# ProProject_FAB-O-MATIC___a_FabLab_machin.net
KiCad netlist of a schematic drawn in EasyEDA Pro
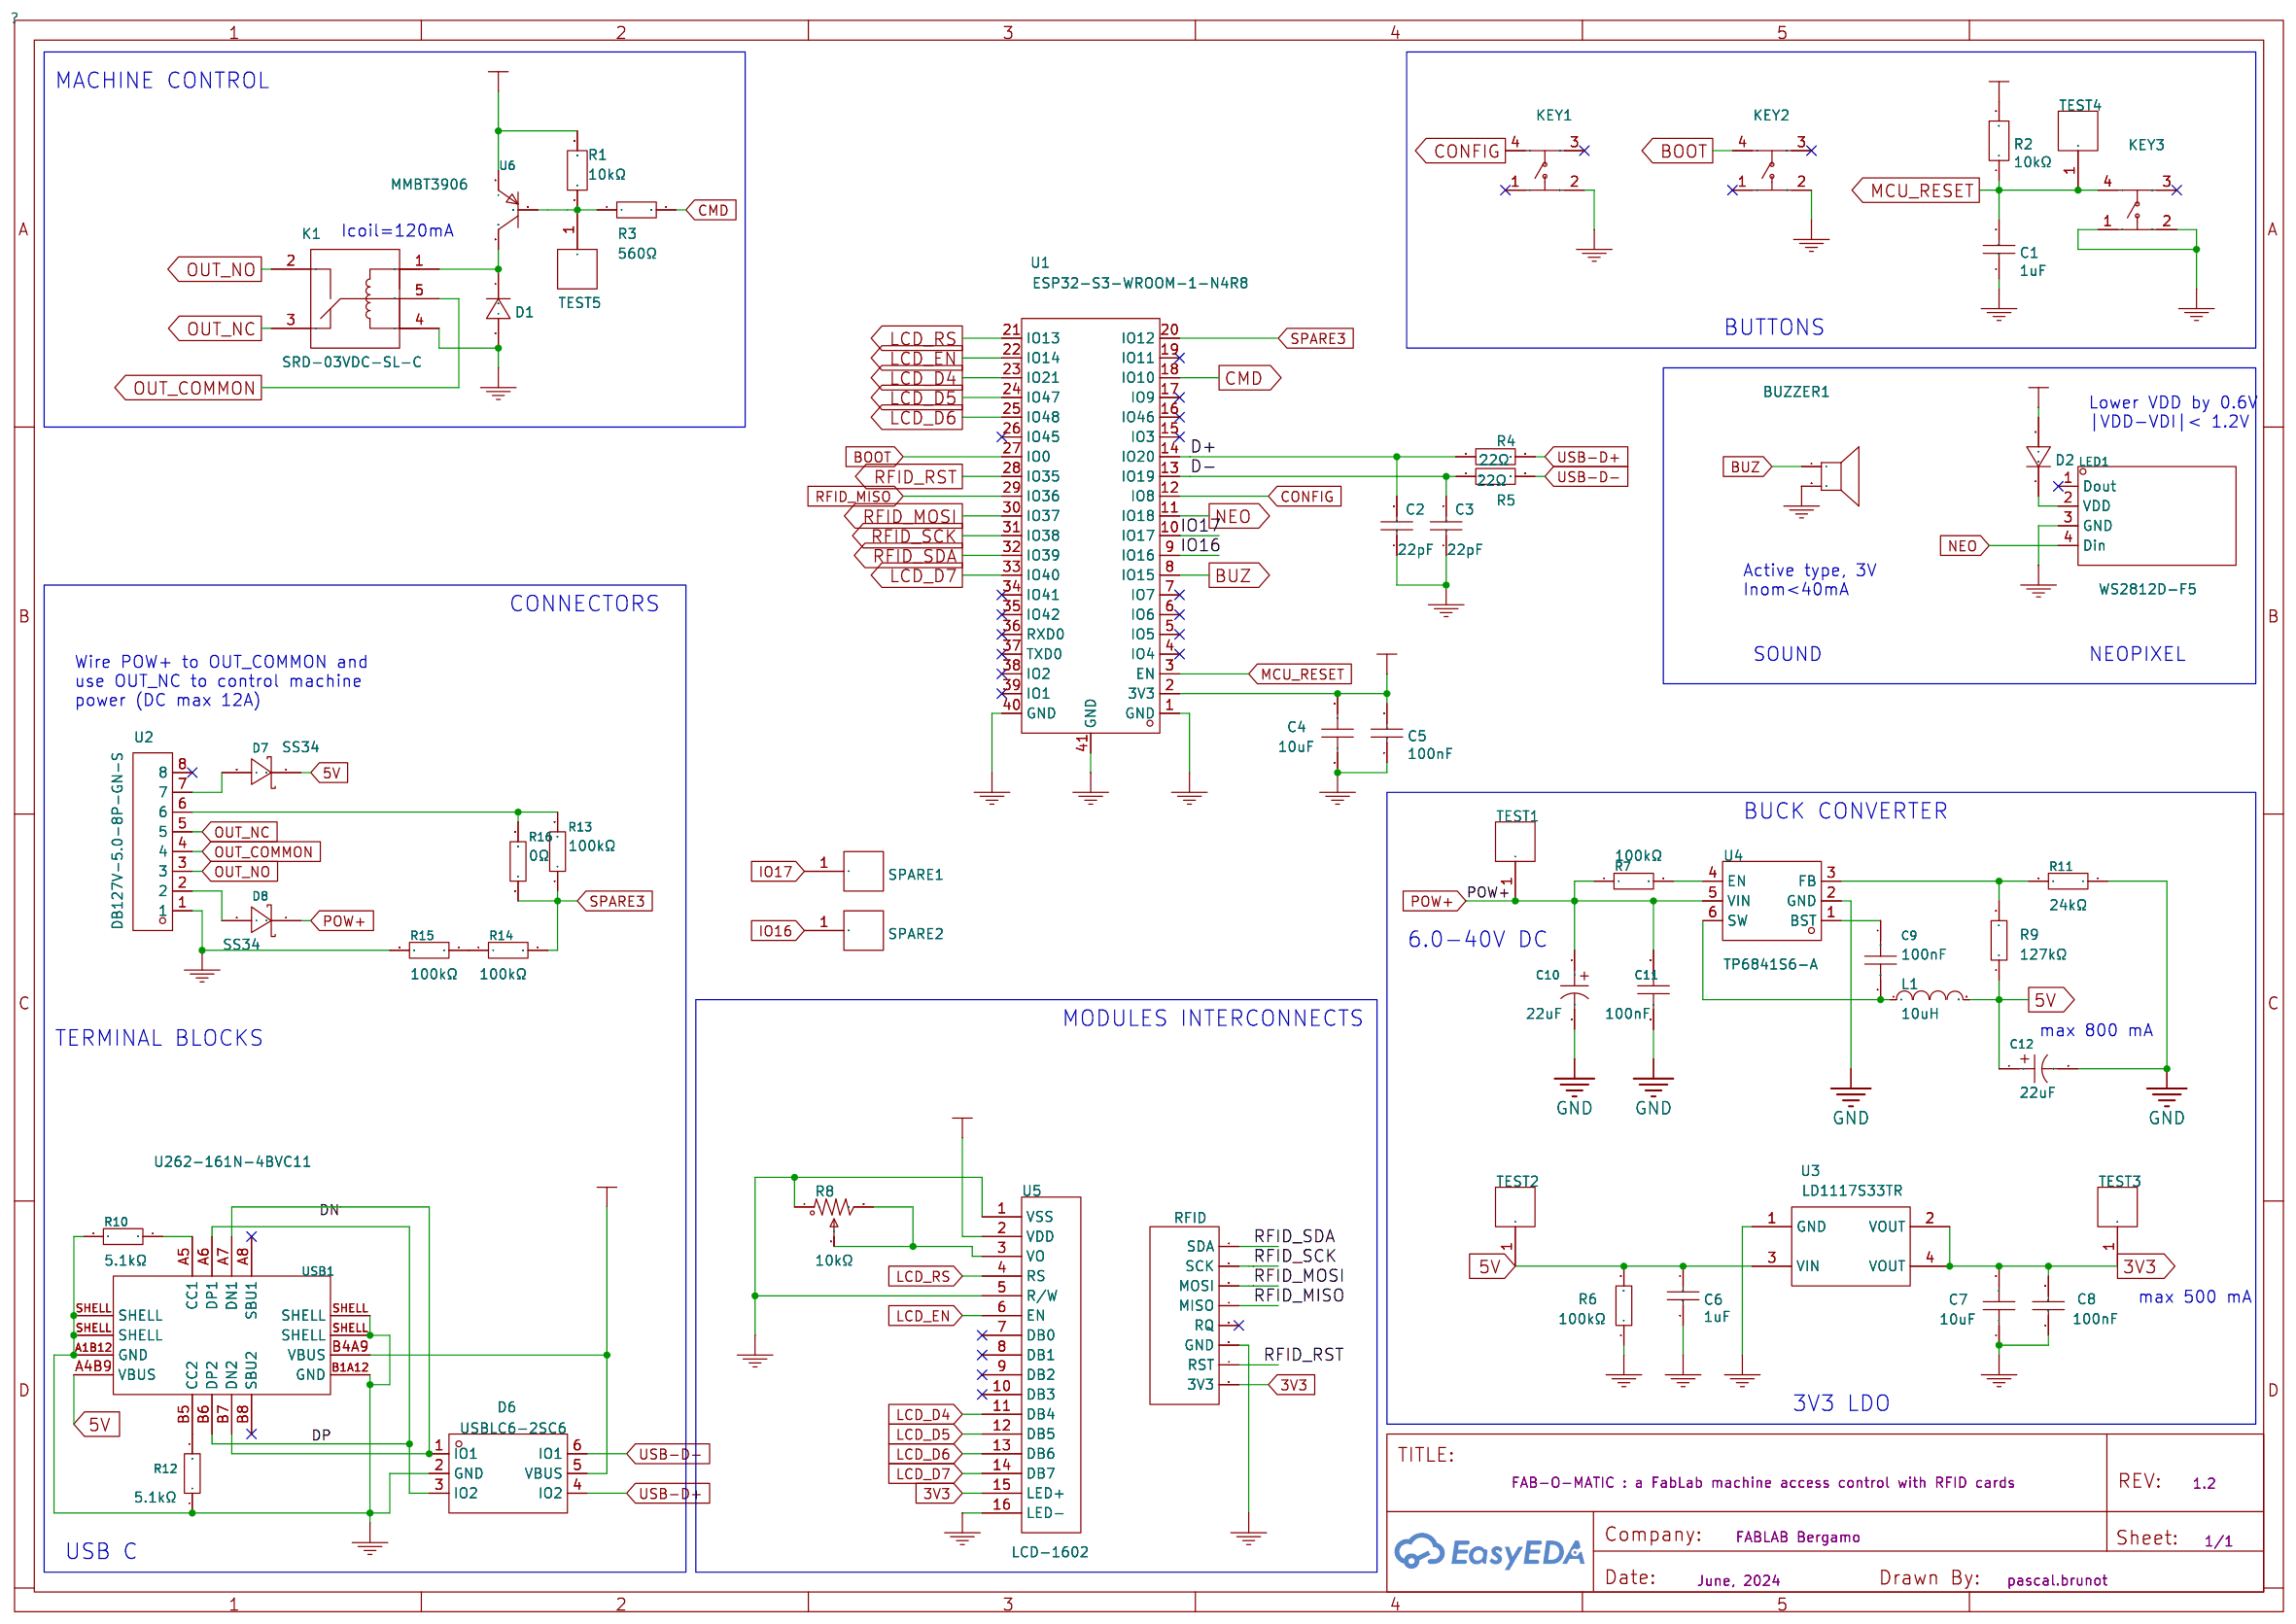
[diagram p0: Schematics]
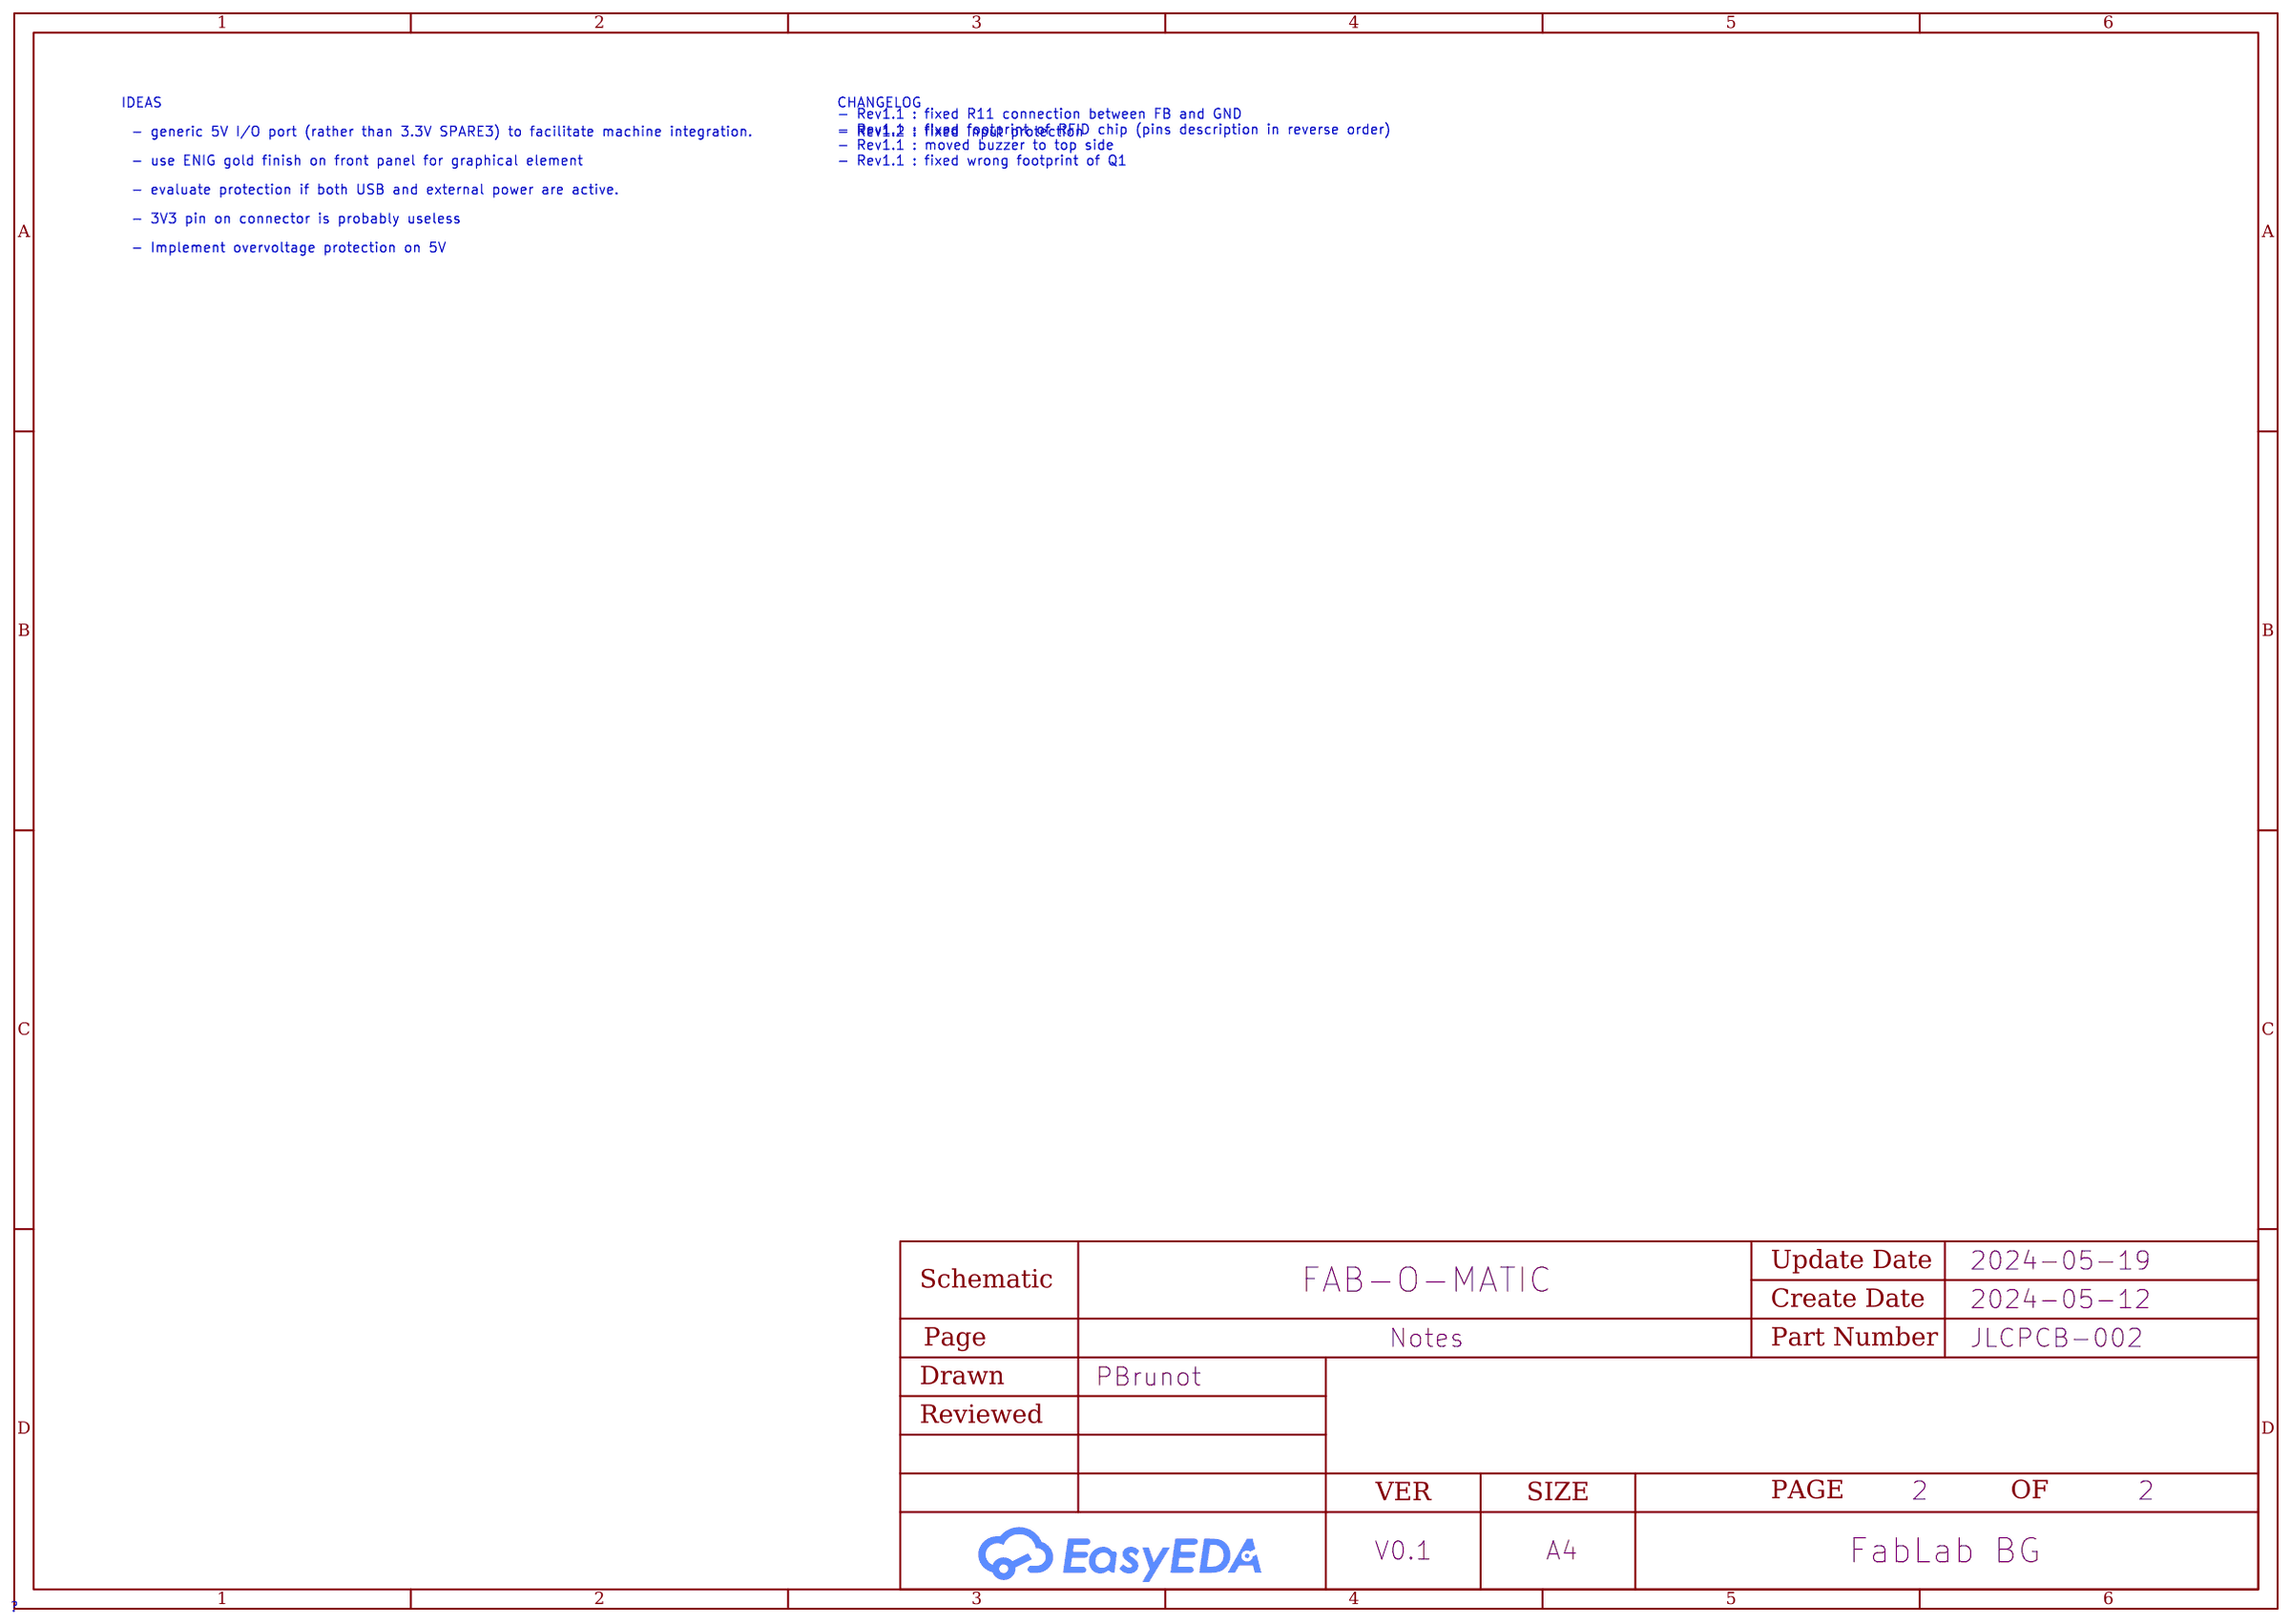
[diagram p1: Notes]

(export (version "E")
  (design (tool "Eeschema 10.0.6"))
  (components
    (comp (ref "BUZZER1")
      (value "4kHz")
      (footprint "easyedapro:footprint_2ee7")
      (fields (field (name "Manufacturer Part") "SFN-12055PA6.5") (field (name "Manufacturer") "S&S(海旭)"))
      (libsource (lib "easyedapro") (part "4000Hz"))
    )
    (comp (ref "C1")
      (value "1uF")
      (footprint "easyedapro:footprint_97e3")
      (fields
        (field (name "Manufacturer Part") "CL21B105KBFNNNE")
        (field (name "Manufacturer") "SAMSUNG(三星)")
      )
      (libsource (lib "easyedapro") (part "1uF"))
    )
    (comp (ref "C2")
      (value "22pF")
      (footprint "easyedapro:footprint_5a9c")
      (fields
        (field (name "Manufacturer Part") "CL10C220JB8NNNC")
        (field (name "Manufacturer") "SAMSUNG(三星)")
      )
      (libsource (lib "easyedapro") (part "22pF"))
    )
    (comp (ref "C3")
      (value "22pF")
      (footprint "easyedapro:footprint_5a9c")
      (fields
        (field (name "Manufacturer Part") "CL10C220JB8NNNC")
        (field (name "Manufacturer") "SAMSUNG(三星)")
      )
      (libsource (lib "easyedapro") (part "22pF"))
    )
    (comp (ref "C4")
      (value "10uF")
      (footprint "easyedapro:footprint_97e3")
      (fields
        (field (name "Manufacturer Part") "GRM21BR61H106KE43L")
        (field (name "Manufacturer") "muRata(村田)")
      )
      (libsource (lib "easyedapro") (part "10uF"))
    )
    (comp (ref "C5")
      (value "100nF")
      (footprint "easyedapro:footprint_97e3")
      (fields
        (field (name "Manufacturer Part") "CL21B104KCFNNNE")
        (field (name "Manufacturer") "SAMSUNG(三星)")
      )
      (libsource (lib "easyedapro") (part "100nF"))
    )
    (comp (ref "C6")
      (value "1uF")
      (footprint "easyedapro:footprint_97e3")
      (fields
        (field (name "Manufacturer Part") "CL21B105KBFNNNE")
        (field (name "Manufacturer") "SAMSUNG(三星)")
      )
      (libsource (lib "easyedapro") (part "1uF"))
    )
    (comp (ref "C7")
      (value "10uF")
      (footprint "easyedapro:footprint_97e3")
      (fields
        (field (name "Manufacturer Part") "GRM21BR61H106KE43L")
        (field (name "Manufacturer") "muRata(村田)")
      )
      (libsource (lib "easyedapro") (part "10uF"))
    )
    (comp (ref "C8")
      (value "100nF")
      (footprint "easyedapro:footprint_97e3")
      (fields
        (field (name "Manufacturer Part") "CL21B104KCFNNNE")
        (field (name "Manufacturer") "SAMSUNG(三星)")
      )
      (libsource (lib "easyedapro") (part "100nF"))
    )
    (comp (ref "C9")
      (value "100nF")
      (footprint "easyedapro:C0603")
      (fields
        (field (name "Manufacturer Part") "CC0603KRX7R9BB104")
        (field (name "Manufacturer") "YAGEO(国巨)")
      )
      (libsource (lib "easyedapro") (part "CC0603KRX7R9BB104"))
    )
    (comp (ref "C10")
      (value "22uF")
      (footprint "easyedapro:CAP-SMD_BD6.3-L6.6-W6.6-FD")
      (fields
        (field (name "Manufacturer Part") "RVT22UF50V67RV0028")
        (field (name "Manufacturer") "KNSCHA(科尼盛)")
      )
      (libsource (lib "easyedapro") (part "RVT22UF50V67RV0028"))
    )
    (comp (ref "C11")
      (value "100nF")
      (footprint "easyedapro:C0603")
      (fields
        (field (name "Manufacturer Part") "CC0603KRX7R9BB104")
        (field (name "Manufacturer") "YAGEO(国巨)")
      )
      (libsource (lib "easyedapro") (part "CC0603KRX7R9BB104"))
    )
    (comp (ref "C12")
      (value "22uF")
      (footprint "easyedapro:CAP-SMD_BD6.3-L6.6-W6.6-FD")
      (fields
        (field (name "Manufacturer Part") "RVT22UF50V67RV0028")
        (field (name "Manufacturer") "KNSCHA(科尼盛)")
      )
      (libsource (lib "easyedapro") (part "RVT22UF50V67RV0028"))
    )
    (comp (ref "D1")
      (value "SM4007PL")
      (footprint "easyedapro:footprint_191e")
      (fields (field (name "Manufacturer") "MDD"))
      (libsource (lib "easyedapro") (part "SM4007PL"))
    )
    (comp (ref "D2")
      (value "SM4007PL")
      (footprint "easyedapro:footprint_191e")
      (fields (field (name "Manufacturer") "MDD"))
      (libsource (lib "easyedapro") (part "SM4007PL"))
    )
    (comp (ref "D6")
      (value "USBLC6-2SC6")
      (footprint "easyedapro:footprint_95a4")
      (fields (field (name "Manufacturer") "TECH PUBLIC(台舟)"))
      (libsource (lib "easyedapro") (part "USBLC6"))
    )
    (comp (ref "D7")
      (value "SS34")
      (footprint "easyedapro:SMA_L4.3-W2.6-LS5.2-RD")
      (fields (field (name "Manufacturer") "MDD"))
      (libsource (lib "easyedapro") (part "SS34_C8678"))
    )
    (comp (ref "D8")
      (value "SS34")
      (footprint "easyedapro:SMA_L4.3-W2.6-LS5.2-RD")
      (fields (field (name "Manufacturer") "MDD"))
      (libsource (lib "easyedapro") (part "SS34_C8678"))
    )
    (comp (ref "K1")
      (value "SRD-03VDC-SL-C")
      (footprint "easyedapro:footprint_4d08")
      (fields (field (name "Manufacturer") "松乐"))
      (libsource (lib "easyedapro") (part "SRD-03VDC-SL-C_C496430"))
    )
    (comp (ref "KEY1")
      (value "TSA063G60-250")
      (footprint "easyedapro:KEY-SMD_4P-L6.1-W6.1-P4.50-LS9.0")
      (fields (field (name "Manufacturer") "BRIGHT(博瑞泰)"))
      (libsource (lib "easyedapro") (part "TSA063G60-250"))
    )
    (comp (ref "KEY2")
      (value "TSA063G60-250")
      (footprint "easyedapro:KEY-SMD_4P-L6.1-W6.1-P4.50-LS9.0")
      (fields (field (name "Manufacturer") "BRIGHT(博瑞泰)"))
      (libsource (lib "easyedapro") (part "TSA063G60-250"))
    )
    (comp (ref "KEY3")
      (value "TSA063G60-250")
      (footprint "easyedapro:KEY-SMD_4P-L6.1-W6.1-P4.50-LS9.0")
      (fields (field (name "Manufacturer") "BRIGHT(博瑞泰)"))
      (libsource (lib "easyedapro") (part "TSA063G60-250"))
    )
    (comp (ref "L1")
      (value "10uH")
      (footprint "easyedapro:IND-SMD_L4.0-W4.0")
      (fields (field (name "Manufacturer Part") "SWPA4030S100MT") (field (name "Manufacturer") "Sunlord(顺络)"))
      (libsource (lib "easyedapro") (part "SWPA4030S100MT"))
    )
    (comp (ref "LED1")
      (value "WS2812D-F5")
      (footprint "easyedapro:LED-TH_4P-BD5.8-P1.30")
      (description "Lamp Holder Type:5mm圆形灯头")
      (fields (field (name "Manufacturer") "worldsemi"))
      (libsource (lib "easyedapro") (part "WS2812D-F5"))
    )
    (comp (ref "P1")
      (value "RFID")
      (footprint "easyedapro:footprint_17af")
      (fields
        (field (name "Manufacturer Part") "Female headerHDR1X8-2.54")
        (field (name "Manufacturer") "BOOMELE")
      )
      (libsource (lib "easyedapro") (part "RFID"))
    )
    (comp (ref "R1")
      (value "10kΩ")
      (footprint "easyedapro:footprint_48ee")
      (fields
        (field (name "Manufacturer Part") "0805W8F1002T5E")
        (field (name "Manufacturer") "UNI-ROYAL(厚声)")
      )
      (libsource (lib "easyedapro") (part "10k"))
    )
    (comp (ref "R2")
      (value "10kΩ")
      (footprint "easyedapro:footprint_48ee")
      (fields
        (field (name "Manufacturer Part") "0805W8F1002T5E")
        (field (name "Manufacturer") "UNI-ROYAL(厚声)")
      )
      (libsource (lib "easyedapro") (part "10k"))
    )
    (comp (ref "R3")
      (value "560Ω")
      (footprint "easyedapro:footprint_6c1d")
      (fields
        (field (name "Manufacturer Part") "0805W8F5600T5E")
        (field (name "Manufacturer") "UNI-ROYAL(厚声)")
      )
      (libsource (lib "easyedapro") (part "560Ω"))
    )
    (comp (ref "R4")
      (value "22Ω")
      (footprint "easyedapro:footprint_48ee")
      (fields
        (field (name "Manufacturer Part") "0603WAF220JT5E")
        (field (name "Manufacturer") "UNI-ROYAL(厚声)")
      )
      (libsource (lib "easyedapro") (part "22"))
    )
    (comp (ref "R5")
      (value "22Ω")
      (footprint "easyedapro:footprint_48ee")
      (fields
        (field (name "Manufacturer Part") "0603WAF220JT5E")
        (field (name "Manufacturer") "UNI-ROYAL(厚声)")
      )
      (libsource (lib "easyedapro") (part "22"))
    )
    (comp (ref "R6")
      (value "100kΩ")
      (footprint "easyedapro:footprint_6c1d")
      (fields
        (field (name "Manufacturer Part") "0805W8F1003T5E")
        (field (name "Manufacturer") "UNI-ROYAL(厚声)")
      )
      (libsource (lib "easyedapro") (part "100kΩ"))
    )
    (comp (ref "R7")
      (value "100kΩ")
      (footprint "easyedapro:R0603")
      (fields
        (field (name "Manufacturer Part") "0603WAF1003T5E")
        (field (name "Manufacturer") "UNI-ROYAL(厚声)")
      )
      (libsource (lib "easyedapro") (part "0603WAF1003T5E"))
    )
    (comp (ref "R8")
      (value "10kΩ")
      (footprint "easyedapro:RES-ADJ-TH_3362P")
      (description "Resistance: Tolerance:±10% Tolerance:±10%")
      (fields (field (name "Manufacturer Part") "3362P-1-103") (field (name "Manufacturer") "BOCHEN(博晨)"))
      (libsource (lib "easyedapro") (part "3362P-1-103_C118956"))
    )
    (comp (ref "R9")
      (value "127kΩ")
      (footprint "easyedapro:R0603")
      (fields (field (name "Manufacturer Part") "RC0603FR-07127KL") (field (name "Manufacturer") "YAGEO(国巨)"))
      (libsource (lib "easyedapro") (part "RC0603FR-07127KL"))
    )
    (comp (ref "R10")
      (value "5.1kΩ")
      (footprint "easyedapro:R0603")
      (fields
        (field (name "Manufacturer Part") "0603WAF5101T5E")
        (field (name "Manufacturer") "UNI-ROYAL(厚声)")
      )
      (libsource (lib "easyedapro") (part "0603WAF5101T5E"))
    )
    (comp (ref "R11")
      (value "24kΩ")
      (footprint "easyedapro:R0603")
      (fields
        (field (name "Manufacturer Part") "0603WAF2402T5E")
        (field (name "Manufacturer") "UNI-ROYAL(厚声)")
      )
      (libsource (lib "easyedapro") (part "0603WAF2402T5E"))
    )
    (comp (ref "R12")
      (value "5.1kΩ")
      (footprint "easyedapro:R0603")
      (fields
        (field (name "Manufacturer Part") "0603WAF5101T5E")
        (field (name "Manufacturer") "UNI-ROYAL(厚声)")
      )
      (libsource (lib "easyedapro") (part "0603WAF5101T5E"))
    )
    (comp (ref "R13")
      (value "100kΩ")
      (footprint "easyedapro:R0603")
      (fields
        (field (name "Manufacturer Part") "0603WAF1003T5E")
        (field (name "Manufacturer") "UNI-ROYAL(厚声)")
      )
      (libsource (lib "easyedapro") (part "0603WAF1003T5E"))
    )
    (comp (ref "R14")
      (value "100kΩ")
      (footprint "easyedapro:R0603")
      (fields
        (field (name "Manufacturer Part") "0603WAF1003T5E")
        (field (name "Manufacturer") "UNI-ROYAL(厚声)")
      )
      (libsource (lib "easyedapro") (part "0603WAF1003T5E"))
    )
    (comp (ref "R15")
      (value "100kΩ")
      (footprint "easyedapro:R0603")
      (fields
        (field (name "Manufacturer Part") "0603WAF1003T5E")
        (field (name "Manufacturer") "UNI-ROYAL(厚声)")
      )
      (libsource (lib "easyedapro") (part "0603WAF1003T5E"))
    )
    (comp (ref "R16")
      (value "0Ω")
      (footprint "easyedapro:R1206")
      (fields
        (field (name "Manufacturer Part") "1206W4F0000T5E")
        (field (name "Manufacturer") "UNI-ROYAL(厚声)")
      )
      (libsource (lib "easyedapro") (part "1206W4F0000T5E"))
    )
    (comp (ref "SPARE1")
      (value "0577-0-43-80-21-27-10-0")
      (footprint "easyedapro:footprint_662d")
      (libsource (lib "easyedapro") (part "0577-0-43-80-21-27-10-0"))
    )
    (comp (ref "SPARE2")
      (value "0577-0-43-80-21-27-10-0")
      (footprint "easyedapro:footprint_662d")
      (libsource (lib "easyedapro") (part "0577-0-43-80-21-27-10-0"))
    )
    (comp (ref "TEST1")
      (value "0577-0-43-80-21-27-10-0")
      (footprint "easyedapro:footprint_662d")
      (libsource (lib "easyedapro") (part "0577-0-43-80-21-27-10-0"))
    )
    (comp (ref "TEST2")
      (value "0577-0-43-80-21-27-10-0")
      (footprint "easyedapro:footprint_662d")
      (libsource (lib "easyedapro") (part "0577-0-43-80-21-27-10-0"))
    )
    (comp (ref "TEST3")
      (value "0577-0-43-80-21-27-10-0")
      (footprint "easyedapro:footprint_662d")
      (libsource (lib "easyedapro") (part "0577-0-43-80-21-27-10-0"))
    )
    (comp (ref "TEST4")
      (value "0577-0-43-80-21-27-10-0")
      (footprint "easyedapro:footprint_662d")
      (libsource (lib "easyedapro") (part "0577-0-43-80-21-27-10-0"))
    )
    (comp (ref "TEST5")
      (value "0577-0-43-80-21-27-10-0")
      (footprint "easyedapro:footprint_662d")
      (libsource (lib "easyedapro") (part "0577-0-43-80-21-27-10-0"))
    )
    (comp (ref "U1")
      (value "ESP32-S3-WROOM-1-N4R8")
      (footprint "easyedapro:footprint_42e8")
      (fields (field (name "Manufacturer") "ESPRESSIF(乐鑫)"))
      (libsource (lib "easyedapro") (part "ESP32-S3-WROOM-1-N4"))
    )
    (comp (ref "U2")
      (value "DB127V-5.0-8P-GN-S")
      (footprint "easyedapro:footprint_42d7")
      (fields (field (name "Manufacturer") "DORABO(地博电气)"))
      (libsource (lib "easyedapro") (part "DB127V-5.0-8P-GN-S"))
    )
    (comp (ref "U3")
      (value "LD1117S33TR")
      (footprint "easyedapro:footprint_da48")
      (fields (field (name "Manufacturer") "ST(意法半导体)"))
      (libsource (lib "easyedapro") (part "LD1117S33TR"))
    )
    (comp (ref "U4")
      (value "TP6841S6-A")
      (footprint "easyedapro:SOT-23-6_L2.9-W1.6-P0.95-LS2.8-BL")
      (fields (field (name "Manufacturer") "TECH PUBLIC(台舟)"))
      (libsource (lib "easyedapro") (part "TP6841S6-A"))
    )
    (comp (ref "U5")
      (value "LCD-1602")
      (footprint "easyedapro:footprint_8a57")
      (fields (field (name "Manufacturer Part") "?"))
      (libsource (lib "easyedapro") (part "LCD-1602"))
    )
    (comp (ref "U6")
      (value "MMBT3906")
      (footprint "easyedapro:SOT-23-3_L2.9-W1.3-P1.90-LS2.4-BR")
      (fields (field (name "Manufacturer") "宏迦橙"))
      (libsource (lib "easyedapro") (part "MMBT3906_C7420354"))
    )
    (comp (ref "USB1")
      (value "U262-161N-4BVC11")
      (footprint "easyedapro:USB-3.1-SMD_U262-161N-4BVC11")
      (fields (field (name "Manufacturer") "XKB Connectivity(中国星坤)"))
      (libsource (lib "easyedapro") (part "U262-16XN-4BVC11"))
    )
  )
  (nets
    (net (code "1") (name "3V3") (class "Default")
      (node (ref "C4") (pin "2") (pinfunction "2_2") (pintype "unspecified"))
      (node (ref "C5") (pin "2") (pinfunction "2_2") (pintype "input"))
      (node (ref "C7") (pin "2") (pinfunction "2_2") (pintype "unspecified"))
      (node (ref "C8") (pin "2") (pinfunction "2_2") (pintype "input"))
      (node (ref "P1") (pin "8") (pinfunction "3V3_8") (pintype "input"))
      (node (ref "R1") (pin "2") (pinfunction "2_2") (pintype "unspecified"))
      (node (ref "R2") (pin "2") (pinfunction "2_2") (pintype "unspecified"))
      (node (ref "TEST3") (pin "1") (pinfunction "1_1") (pintype "unspecified"))
      (node (ref "U1") (pin "2") (pinfunction "3V3_2") (pintype "unspecified"))
      (node (ref "U3") (pin "2") (pinfunction "VOUT_2") (pintype "unspecified"))
      (node (ref "U3") (pin "4") (pinfunction "VOUT_4") (pintype "unspecified"))
      (node (ref "U5") (pin "15") (pinfunction "LED+_15") (pintype "unspecified"))
      (node (ref "U6") (pin "2") (pinfunction "E_2") (pintype "input"))
    )
    (net (code "2") (name "5V") (class "Default")
      (node (ref "C12") (pin "1") (pinfunction "1_1") (pintype "input"))
      (node (ref "C6") (pin "1") (pinfunction "1_1") (pintype "input"))
      (node (ref "D2") (pin "2") (pinfunction "A_2") (pintype "unspecified"))
      (node (ref "D6") (pin "5") (pinfunction "VBUS_5") (pintype "unspecified"))
      (node (ref "D7") (pin "1") (pinfunction "K_1") (pintype "input"))
      (node (ref "L1") (pin "2") (pinfunction "2_2") (pintype "input"))
      (node (ref "R6") (pin "2") (pinfunction "2_2") (pintype "unspecified"))
      (node (ref "R9") (pin "1") (pinfunction "1_1") (pintype "unspecified"))
      (node (ref "TEST2") (pin "1") (pinfunction "1_1") (pintype "unspecified"))
      (node (ref "U3") (pin "3") (pinfunction "VIN_3") (pintype "unspecified"))
      (node (ref "U5") (pin "2") (pinfunction "VDD_2") (pintype "unspecified"))
      (node (ref "USB1") (pin "A4B9") (pinfunction "VBUS_A4B9") (pintype "input"))
      (node (ref "USB1") (pin "B4A9") (pinfunction "VBUS_B4A9") (pintype "input"))
    )
    (net (code "3") (name "BOOT") (class "Default")
      (node (ref "KEY2") (pin "4") (pinfunction "4_4") (pintype "input"))
      (node (ref "U1") (pin "27") (pinfunction "IO0_27") (pintype "unspecified"))
    )
    (net (code "4") (name "BUZ") (class "Default")
      (node (ref "BUZZER1") (pin "1") (pinfunction "1_1") (pintype "unspecified"))
      (node (ref "U1") (pin "8") (pinfunction "IO15_8") (pintype "unspecified"))
    )
    (net (code "5") (name "CMD") (class "Default")
      (node (ref "R3") (pin "2") (pinfunction "2_2") (pintype "input"))
      (node (ref "U1") (pin "18") (pinfunction "IO10_18") (pintype "unspecified"))
    )
    (net (code "6") (name "CONFIG") (class "Default")
      (node (ref "KEY1") (pin "4") (pinfunction "4_4") (pintype "input"))
      (node (ref "U1") (pin "12") (pinfunction "IO8_12") (pintype "unspecified"))
    )
    (net (code "7") (name "D+") (class "Default")
      (node (ref "C2") (pin "2") (pinfunction "2_2") (pintype "input"))
      (node (ref "R4") (pin "1") (pinfunction "1_1") (pintype "input"))
      (node (ref "U1") (pin "14") (pinfunction "IO20_14") (pintype "unspecified"))
    )
    (net (code "8") (name "D-") (class "Default")
      (node (ref "C3") (pin "2") (pinfunction "2_2") (pintype "input"))
      (node (ref "R5") (pin "1") (pinfunction "1_1") (pintype "input"))
      (node (ref "U1") (pin "13") (pinfunction "IO19_13") (pintype "unspecified"))
    )
    (net (code "9") (name "DN") (class "Default")
      (node (ref "D6") (pin "1") (pinfunction "IO1_1") (pintype "unspecified"))
      (node (ref "USB1") (pin "A7") (pinfunction "DN1_A7") (pintype "input"))
      (node (ref "USB1") (pin "B7") (pinfunction "DN2_B7") (pintype "input"))
    )
    (net (code "10") (name "DP") (class "Default")
      (node (ref "D6") (pin "3") (pinfunction "IO2_3") (pintype "unspecified"))
      (node (ref "USB1") (pin "A6") (pinfunction "DP1_A6") (pintype "input"))
      (node (ref "USB1") (pin "B6") (pinfunction "DP2_B6") (pintype "input"))
    )
    (net (code "11") (name "GND") (class "Default")
      (node (ref "BUZZER1") (pin "2") (pinfunction "2_2") (pintype "unspecified"))
      (node (ref "C1") (pin "1") (pinfunction "1_1") (pintype "input"))
      (node (ref "C10") (pin "2") (pinfunction "2_2") (pintype "input"))
      (node (ref "C11") (pin "1") (pinfunction "1_1") (pintype "input"))
      (node (ref "C12") (pin "2") (pinfunction "2_2") (pintype "input"))
      (node (ref "C2") (pin "1") (pinfunction "1_1") (pintype "input"))
      (node (ref "C3") (pin "1") (pinfunction "1_1") (pintype "input"))
      (node (ref "C4") (pin "1") (pinfunction "1_1") (pintype "unspecified"))
      (node (ref "C5") (pin "1") (pinfunction "1_1") (pintype "input"))
      (node (ref "C6") (pin "2") (pinfunction "2_2") (pintype "input"))
      (node (ref "C7") (pin "1") (pinfunction "1_1") (pintype "unspecified"))
      (node (ref "C8") (pin "1") (pinfunction "1_1") (pintype "input"))
      (node (ref "D1") (pin "2") (pinfunction "A_2") (pintype "unspecified"))
      (node (ref "D6") (pin "2") (pinfunction "GND_2") (pintype "unspecified"))
      (node (ref "K1") (pin "4") (pinfunction "4_4") (pintype "unspecified"))
      (node (ref "KEY1") (pin "2") (pinfunction "2_2") (pintype "input"))
      (node (ref "KEY2") (pin "2") (pinfunction "2_2") (pintype "input"))
      (node (ref "KEY3") (pin "1") (pinfunction "1_1") (pintype "input"))
      (node (ref "KEY3") (pin "2") (pinfunction "2_2") (pintype "input"))
      (node (ref "LED1") (pin "3") (pinfunction "GND_3") (pintype "input"))
      (node (ref "P1") (pin "6") (pinfunction "GND_6") (pintype "input"))
      (node (ref "R10") (pin "2") (pinfunction "2_2") (pintype "input"))
      (node (ref "R11") (pin "1") (pinfunction "1_1") (pintype "input"))
      (node (ref "R12") (pin "1") (pinfunction "1_1") (pintype "input"))
      (node (ref "R15") (pin "2") (pinfunction "2_2") (pintype "input"))
      (node (ref "R6") (pin "1") (pinfunction "1_1") (pintype "unspecified"))
      (node (ref "R8") (pin "1") (pinfunction "1_1") (pintype "input"))
      (node (ref "U1") (pin "1") (pinfunction "GND_1") (pintype "unspecified"))
      (node (ref "U1") (pin "40") (pinfunction "GND_40") (pintype "unspecified"))
      (node (ref "U1") (pin "41") (pinfunction "GND_41") (pintype "unspecified"))
      (node (ref "U2") (pin "1") (pinfunction "1_1") (pintype "unspecified"))
      (node (ref "U3") (pin "1") (pinfunction "GND_1") (pintype "unspecified"))
      (node (ref "U4") (pin "2") (pinfunction "GND_2") (pintype "input"))
      (node (ref "U5") (pin "1") (pinfunction "VSS_1") (pintype "unspecified"))
      (node (ref "U5") (pin "16") (pinfunction "LED-_16") (pintype "unspecified"))
      (node (ref "U5") (pin "5") (pinfunction "R/W_5") (pintype "unspecified"))
      (node (ref "USB1") (pin "A1B12") (pinfunction "GND_A1B12") (pintype "input"))
      (node (ref "USB1") (pin "B1A12") (pinfunction "GND_B1A12") (pintype "input"))
      (node (ref "USB1") (pin "SHELL") (pinfunction "SHELL_SHELL") (pintype "input"))
    )
    (net (code "12") (name "IO16") (class "Default")
      (node (ref "SPARE2") (pin "1") (pinfunction "1_1") (pintype "unspecified"))
      (node (ref "U1") (pin "9") (pinfunction "IO16_9") (pintype "unspecified"))
    )
    (net (code "13") (name "IO17") (class "Default")
      (node (ref "SPARE1") (pin "1") (pinfunction "1_1") (pintype "unspecified"))
      (node (ref "U1") (pin "10") (pinfunction "IO17_10") (pintype "unspecified"))
    )
    (net (code "14") (name "LCD_D4") (class "Default")
      (node (ref "U1") (pin "23") (pinfunction "IO21_23") (pintype "unspecified"))
      (node (ref "U5") (pin "11") (pinfunction "DB4_11") (pintype "unspecified"))
    )
    (net (code "15") (name "LCD_D5") (class "Default")
      (node (ref "U1") (pin "24") (pinfunction "IO47_24") (pintype "unspecified"))
      (node (ref "U5") (pin "12") (pinfunction "DB5_12") (pintype "unspecified"))
    )
    (net (code "16") (name "LCD_D6") (class "Default")
      (node (ref "U1") (pin "25") (pinfunction "IO48_25") (pintype "unspecified"))
      (node (ref "U5") (pin "13") (pinfunction "DB6_13") (pintype "unspecified"))
    )
    (net (code "17") (name "LCD_D7") (class "Default")
      (node (ref "U1") (pin "33") (pinfunction "IO40_33") (pintype "unspecified"))
      (node (ref "U5") (pin "14") (pinfunction "DB7_14") (pintype "unspecified"))
    )
    (net (code "18") (name "LCD_EN") (class "Default")
      (node (ref "U1") (pin "22") (pinfunction "IO14_22") (pintype "unspecified"))
      (node (ref "U5") (pin "6") (pinfunction "EN_6") (pintype "unspecified"))
    )
    (net (code "19") (name "LCD_RS") (class "Default")
      (node (ref "U1") (pin "21") (pinfunction "IO13_21") (pintype "unspecified"))
      (node (ref "U5") (pin "4") (pinfunction "RS_4") (pintype "unspecified"))
    )
    (net (code "20") (name "MCU_RESET") (class "Default")
      (node (ref "C1") (pin "2") (pinfunction "2_2") (pintype "input"))
      (node (ref "KEY3") (pin "4") (pinfunction "4_4") (pintype "input"))
      (node (ref "R2") (pin "1") (pinfunction "1_1") (pintype "unspecified"))
      (node (ref "TEST4") (pin "1") (pinfunction "1_1") (pintype "unspecified"))
      (node (ref "U1") (pin "3") (pinfunction "EN_3") (pintype "unspecified"))
    )
    (net (code "21") (name "NEO") (class "Default")
      (node (ref "LED1") (pin "4") (pinfunction "Din_4") (pintype "input"))
      (node (ref "U1") (pin "11") (pinfunction "IO18_11") (pintype "unspecified"))
    )
    (net (code "22") (name "Net-(D1-C)") (class "Default")
      (node (ref "D1") (pin "1") (pinfunction "C_1") (pintype "unspecified"))
      (node (ref "K1") (pin "1") (pinfunction "1_1") (pintype "unspecified"))
      (node (ref "U6") (pin "3") (pinfunction "C_3") (pintype "input"))
    )
    (net (code "23") (name "Net-(D2-C)") (class "Default")
      (node (ref "D2") (pin "1") (pinfunction "C_1") (pintype "unspecified"))
      (node (ref "LED1") (pin "2") (pinfunction "VDD_2") (pintype "input"))
    )
    (net (code "24") (name "Net-(D7-A)") (class "Default")
      (node (ref "D7") (pin "2") (pinfunction "A_2") (pintype "input"))
      (node (ref "U2") (pin "7") (pinfunction "7_7") (pintype "unspecified"))
    )
    (net (code "25") (name "Net-(D8-A)") (class "Default")
      (node (ref "D8") (pin "2") (pinfunction "A_2") (pintype "input"))
      (node (ref "U2") (pin "2") (pinfunction "2_2") (pintype "unspecified"))
    )
    (net (code "26") (name "Net-(R13-Pad2)") (class "Default")
      (node (ref "R13") (pin "2") (pinfunction "2_2") (pintype "input"))
      (node (ref "R16") (pin "2") (pinfunction "2_2") (pintype "input"))
      (node (ref "U2") (pin "6") (pinfunction "6_6") (pintype "unspecified"))
    )
    (net (code "27") (name "Net-(R14-Pad1)") (class "Default")
      (node (ref "R14") (pin "1") (pinfunction "1_1") (pintype "input"))
      (node (ref "R15") (pin "1") (pinfunction "1_1") (pintype "input"))
    )
    (net (code "28") (name "Net-(U4-BST)") (class "Default")
      (node (ref "C9") (pin "1") (pinfunction "1_1") (pintype "input"))
      (node (ref "U4") (pin "1") (pinfunction "BST_1") (pintype "input"))
    )
    (net (code "29") (name "Net-(U4-EN)") (class "Default")
      (node (ref "R7") (pin "2") (pinfunction "2_2") (pintype "input"))
      (node (ref "U4") (pin "4") (pinfunction "EN_4") (pintype "input"))
    )
    (net (code "30") (name "Net-(U4-FB)") (class "Default")
      (node (ref "R11") (pin "2") (pinfunction "2_2") (pintype "input"))
      (node (ref "R9") (pin "2") (pinfunction "2_2") (pintype "unspecified"))
      (node (ref "U4") (pin "3") (pinfunction "FB_3") (pintype "input"))
    )
    (net (code "31") (name "Net-(U4-SW)") (class "Default")
      (node (ref "C9") (pin "2") (pinfunction "2_2") (pintype "input"))
      (node (ref "L1") (pin "1") (pinfunction "1_1") (pintype "input"))
      (node (ref "U4") (pin "6") (pinfunction "SW_6") (pintype "input"))
    )
    (net (code "32") (name "Net-(U5-VO)") (class "Default")
      (node (ref "R8") (pin "2") (pinfunction "2_2") (pintype "input"))
      (node (ref "R8") (pin "3") (pinfunction "3_3") (pintype "input"))
      (node (ref "U5") (pin "3") (pinfunction "VO_3") (pintype "unspecified"))
    )
    (net (code "33") (name "Net-(U6-B)") (class "Default")
      (node (ref "R1") (pin "1") (pinfunction "1_1") (pintype "unspecified"))
      (node (ref "R3") (pin "1") (pinfunction "1_1") (pintype "input"))
      (node (ref "TEST5") (pin "1") (pinfunction "1_1") (pintype "unspecified"))
      (node (ref "U6") (pin "1") (pinfunction "B_1") (pintype "input"))
    )
    (net (code "34") (name "Net-(USB1-CC1)") (class "Default")
      (node (ref "R10") (pin "1") (pinfunction "1_1") (pintype "input"))
      (node (ref "USB1") (pin "A5") (pinfunction "CC1_A5") (pintype "input"))
    )
    (net (code "35") (name "Net-(USB1-CC2)") (class "Default")
      (node (ref "R12") (pin "2") (pinfunction "2_2") (pintype "input"))
      (node (ref "USB1") (pin "B5") (pinfunction "CC2_B5") (pintype "input"))
    )
    (net (code "36") (name "OUT_COMMON") (class "Default")
      (node (ref "K1") (pin "5") (pinfunction "5_5") (pintype "unspecified"))
      (node (ref "U2") (pin "4") (pinfunction "4_4") (pintype "unspecified"))
    )
    (net (code "37") (name "OUT_NC") (class "Default")
      (node (ref "K1") (pin "3") (pinfunction "3_3") (pintype "unspecified"))
      (node (ref "U2") (pin "5") (pinfunction "5_5") (pintype "unspecified"))
    )
    (net (code "38") (name "OUT_NO") (class "Default")
      (node (ref "K1") (pin "2") (pinfunction "2_2") (pintype "unspecified"))
      (node (ref "U2") (pin "3") (pinfunction "3_3") (pintype "unspecified"))
    )
    (net (code "39") (name "POW+") (class "Default")
      (node (ref "C10") (pin "1") (pinfunction "1_1") (pintype "input"))
      (node (ref "C11") (pin "2") (pinfunction "2_2") (pintype "input"))
      (node (ref "D8") (pin "1") (pinfunction "K_1") (pintype "input"))
      (node (ref "R7") (pin "1") (pinfunction "1_1") (pintype "input"))
      (node (ref "TEST1") (pin "1") (pinfunction "1_1") (pintype "unspecified"))
      (node (ref "U4") (pin "5") (pinfunction "VIN_5") (pintype "input"))
    )
    (net (code "40") (name "RFID_MISO") (class "Default")
      (node (ref "P1") (pin "4") (pinfunction "MISO_4") (pintype "input"))
      (node (ref "U1") (pin "29") (pinfunction "IO36_29") (pintype "unspecified"))
    )
    (net (code "41") (name "RFID_MOSI") (class "Default")
      (node (ref "P1") (pin "3") (pinfunction "MOSI_3") (pintype "input"))
      (node (ref "U1") (pin "30") (pinfunction "IO37_30") (pintype "unspecified"))
    )
    (net (code "42") (name "RFID_RST") (class "Default")
      (node (ref "P1") (pin "7") (pinfunction "RST_7") (pintype "input"))
      (node (ref "U1") (pin "28") (pinfunction "IO35_28") (pintype "unspecified"))
    )
    (net (code "43") (name "RFID_SCK") (class "Default")
      (node (ref "P1") (pin "2") (pinfunction "SCK_2") (pintype "input"))
      (node (ref "U1") (pin "31") (pinfunction "IO38_31") (pintype "unspecified"))
    )
    (net (code "44") (name "RFID_SDA") (class "Default")
      (node (ref "P1") (pin "1") (pinfunction "SDA_1") (pintype "input"))
      (node (ref "U1") (pin "32") (pinfunction "IO39_32") (pintype "unspecified"))
    )
    (net (code "45") (name "SPARE3") (class "Default")
      (node (ref "R13") (pin "1") (pinfunction "1_1") (pintype "input"))
      (node (ref "R14") (pin "2") (pinfunction "2_2") (pintype "input"))
      (node (ref "R16") (pin "1") (pinfunction "1_1") (pintype "input"))
      (node (ref "U1") (pin "20") (pinfunction "IO12_20") (pintype "unspecified"))
    )
    (net (code "46") (name "USB-D+") (class "Default")
      (node (ref "D6") (pin "4") (pinfunction "IO2_4") (pintype "unspecified"))
      (node (ref "R4") (pin "2") (pinfunction "2_2") (pintype "input"))
    )
    (net (code "47") (name "USB-D-") (class "Default")
      (node (ref "D6") (pin "6") (pinfunction "IO1_6") (pintype "unspecified"))
      (node (ref "R5") (pin "2") (pinfunction "2_2") (pintype "input"))
    )
    (net (code "48") (name "unconnected-(KEY1-Pad1)") (class "Default")
      (node (ref "KEY1") (pin "1") (pinfunction "1_1") (pintype "input+no_connect"))
    )
    (net (code "49") (name "unconnected-(KEY1-Pad3)") (class "Default")
      (node (ref "KEY1") (pin "3") (pinfunction "3_3") (pintype "input+no_connect"))
    )
    (net (code "50") (name "unconnected-(KEY2-Pad1)") (class "Default")
      (node (ref "KEY2") (pin "1") (pinfunction "1_1") (pintype "input+no_connect"))
    )
    (net (code "51") (name "unconnected-(KEY2-Pad3)") (class "Default")
      (node (ref "KEY2") (pin "3") (pinfunction "3_3") (pintype "input+no_connect"))
    )
    (net (code "52") (name "unconnected-(KEY3-Pad3)") (class "Default")
      (node (ref "KEY3") (pin "3") (pinfunction "3_3") (pintype "input+no_connect"))
    )
    (net (code "53") (name "unconnected-(LED1-Dout-Pad1)") (class "Default")
      (node (ref "LED1") (pin "1") (pinfunction "Dout_1") (pintype "input+no_connect"))
    )
    (net (code "54") (name "unconnected-(P1-RQ-Pad5)") (class "Default")
      (node (ref "P1") (pin "5") (pinfunction "RQ_5") (pintype "input+no_connect"))
    )
    (net (code "55") (name "unconnected-(U1-IO1-Pad39)") (class "Default")
      (node (ref "U1") (pin "39") (pinfunction "IO1_39") (pintype "unspecified+no_connect"))
    )
    (net (code "56") (name "unconnected-(U1-IO2-Pad38)") (class "Default")
      (node (ref "U1") (pin "38") (pinfunction "IO2_38") (pintype "unspecified+no_connect"))
    )
    (net (code "57") (name "unconnected-(U1-IO3-Pad15)") (class "Default")
      (node (ref "U1") (pin "15") (pinfunction "IO3_15") (pintype "unspecified+no_connect"))
    )
    (net (code "58") (name "unconnected-(U1-IO4-Pad4)") (class "Default")
      (node (ref "U1") (pin "4") (pinfunction "IO4_4") (pintype "unspecified+no_connect"))
    )
    (net (code "59") (name "unconnected-(U1-IO5-Pad5)") (class "Default")
      (node (ref "U1") (pin "5") (pinfunction "IO5_5") (pintype "unspecified+no_connect"))
    )
    (net (code "60") (name "unconnected-(U1-IO6-Pad6)") (class "Default")
      (node (ref "U1") (pin "6") (pinfunction "IO6_6") (pintype "unspecified+no_connect"))
    )
    (net (code "61") (name "unconnected-(U1-IO7-Pad7)") (class "Default")
      (node (ref "U1") (pin "7") (pinfunction "IO7_7") (pintype "unspecified+no_connect"))
    )
    (net (code "62") (name "unconnected-(U1-IO9-Pad17)") (class "Default")
      (node (ref "U1") (pin "17") (pinfunction "IO9_17") (pintype "unspecified+no_connect"))
    )
    (net (code "63") (name "unconnected-(U1-IO11-Pad19)") (class "Default")
      (node (ref "U1") (pin "19") (pinfunction "IO11_19") (pintype "unspecified+no_connect"))
    )
    (net (code "64") (name "unconnected-(U1-IO41-Pad34)") (class "Default")
      (node (ref "U1") (pin "34") (pinfunction "IO41_34") (pintype "unspecified+no_connect"))
    )
    (net (code "65") (name "unconnected-(U1-IO42-Pad35)") (class "Default")
      (node (ref "U1") (pin "35") (pinfunction "IO42_35") (pintype "unspecified+no_connect"))
    )
    (net (code "66") (name "unconnected-(U1-IO45-Pad26)") (class "Default")
      (node (ref "U1") (pin "26") (pinfunction "IO45_26") (pintype "unspecified+no_connect"))
    )
    (net (code "67") (name "unconnected-(U1-IO46-Pad16)") (class "Default")
      (node (ref "U1") (pin "16") (pinfunction "IO46_16") (pintype "unspecified+no_connect"))
    )
    (net (code "68") (name "unconnected-(U1-RXD0-Pad36)") (class "Default")
      (node (ref "U1") (pin "36") (pinfunction "RXD0_36") (pintype "unspecified+no_connect"))
    )
    (net (code "69") (name "unconnected-(U1-TXD0-Pad37)") (class "Default")
      (node (ref "U1") (pin "37") (pinfunction "TXD0_37") (pintype "unspecified+no_connect"))
    )
    (net (code "70") (name "unconnected-(U2-Pad8)") (class "Default")
      (node (ref "U2") (pin "8") (pinfunction "8_8") (pintype "unspecified+no_connect"))
    )
    (net (code "71") (name "unconnected-(U5-DB0-Pad7)") (class "Default")
      (node (ref "U5") (pin "7") (pinfunction "DB0_7") (pintype "unspecified+no_connect"))
    )
    (net (code "72") (name "unconnected-(U5-DB1-Pad8)") (class "Default")
      (node (ref "U5") (pin "8") (pinfunction "DB1_8") (pintype "unspecified+no_connect"))
    )
    (net (code "73") (name "unconnected-(U5-DB2-Pad9)") (class "Default")
      (node (ref "U5") (pin "9") (pinfunction "DB2_9") (pintype "unspecified+no_connect"))
    )
    (net (code "74") (name "unconnected-(U5-DB3-Pad10)") (class "Default")
      (node (ref "U5") (pin "10") (pinfunction "DB3_10") (pintype "unspecified+no_connect"))
    )
    (net (code "75") (name "unconnected-(USB1-SBU1-PadA8)") (class "Default")
      (node (ref "USB1") (pin "A8") (pinfunction "SBU1_A8") (pintype "input+no_connect"))
    )
    (net (code "76") (name "unconnected-(USB1-SBU2-PadB8)") (class "Default")
      (node (ref "USB1") (pin "B8") (pinfunction "SBU2_B8") (pintype "input+no_connect"))
    )
  )
)
